# queso_dip_v4_5.net
KiCad netlist of a schematic drawn in EAGLE
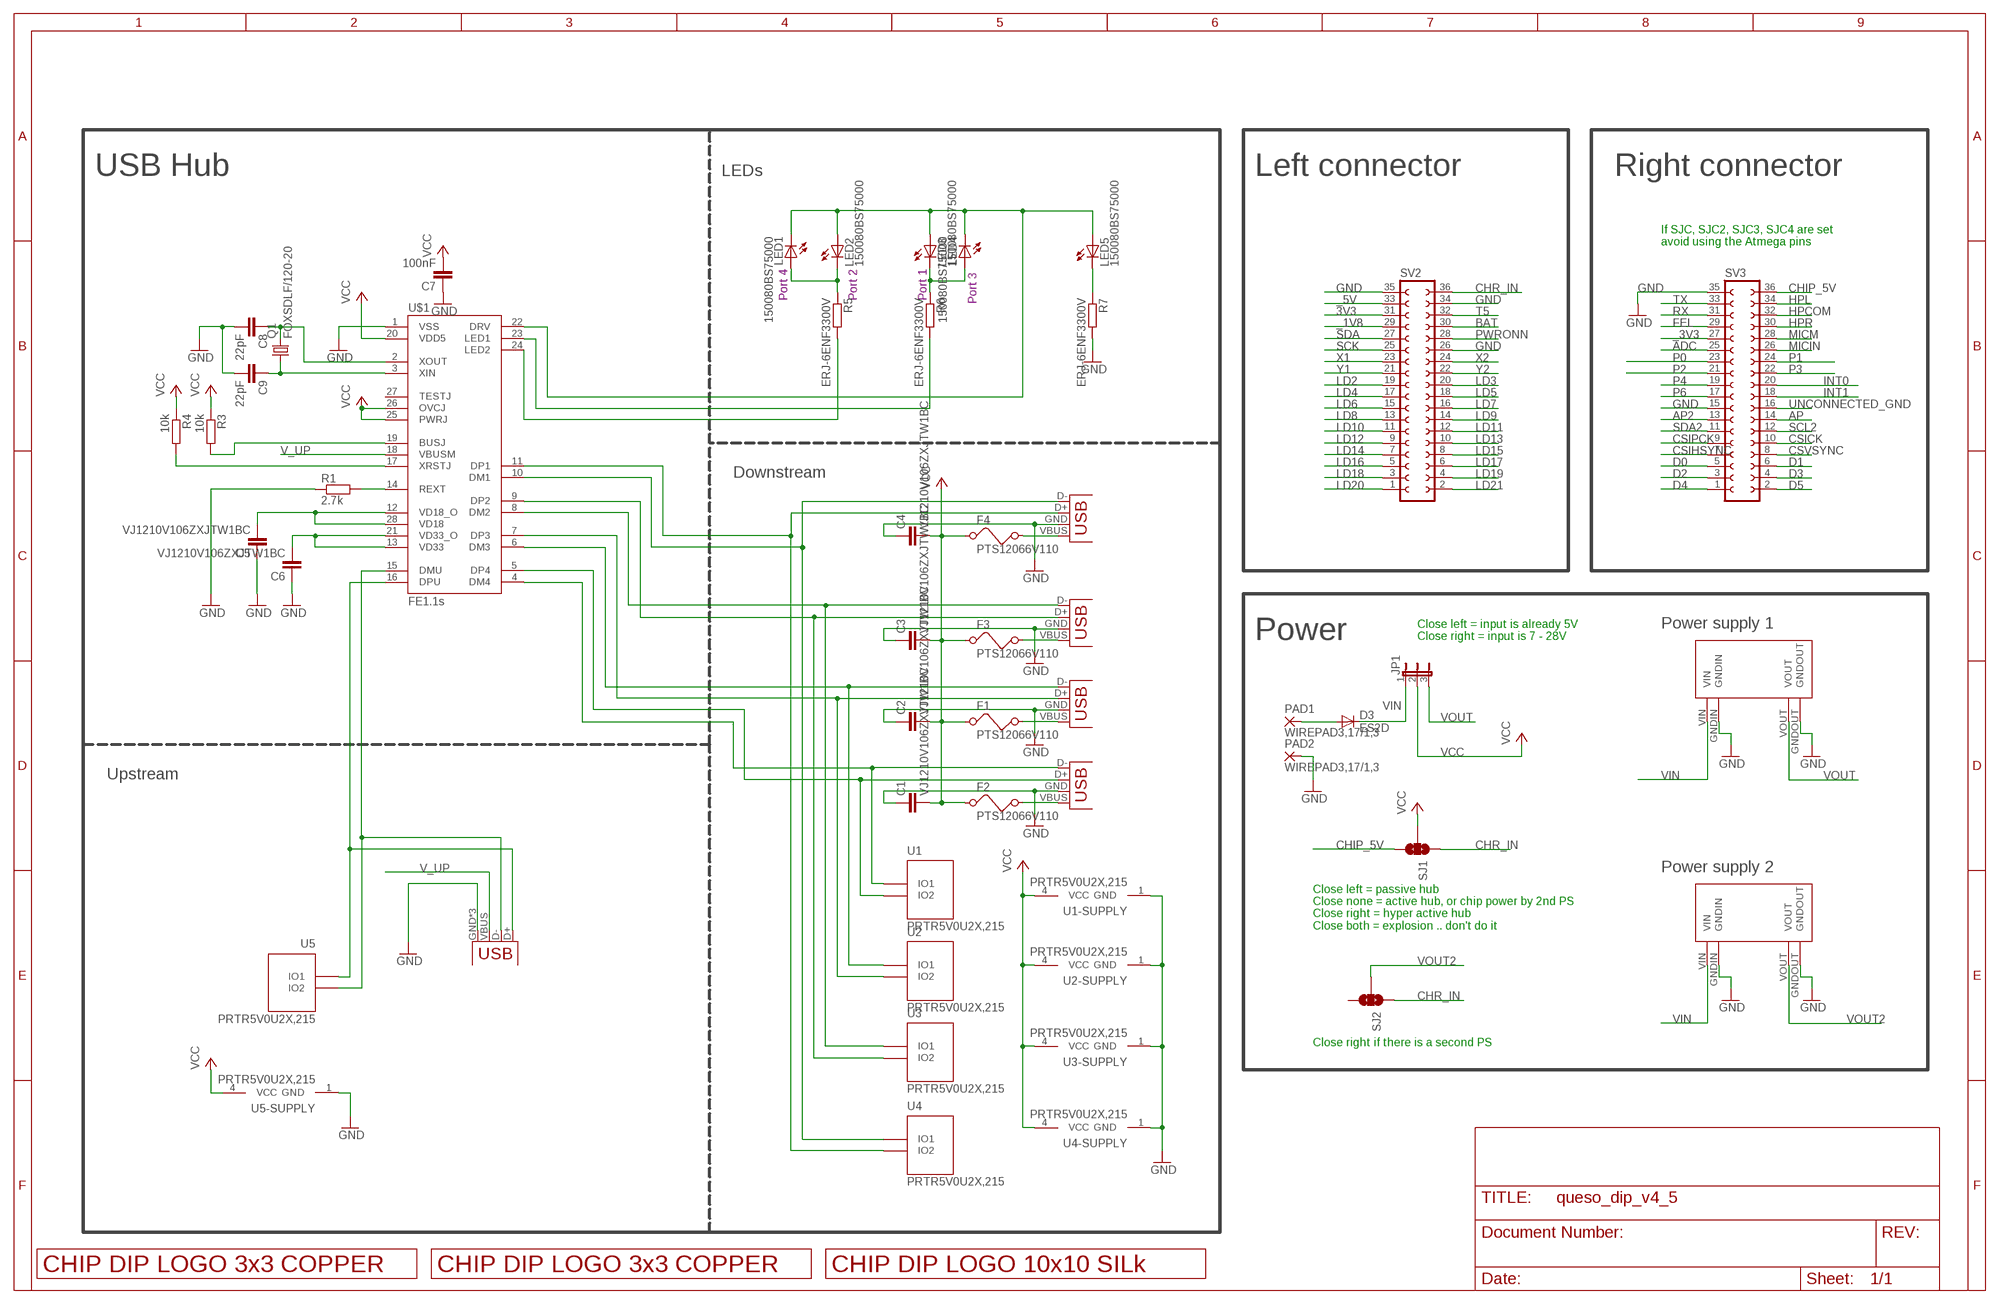
[diagram p0: schematic, sheet 1]

(export (version "E")
  (design (tool "Eeschema 10.0.6"))
  (components
    (comp (ref "C1")
      (value "VJ1210V106ZXJTW1BC")
      (footprint "eagle-import:C1210")
      (libsource (lib "eagle-import") (part "C-EUC1210"))
    )
    (comp (ref "C2")
      (value "VJ1210V106ZXJTW1BC")
      (footprint "eagle-import:C1210")
      (libsource (lib "eagle-import") (part "C-EUC1210"))
    )
    (comp (ref "C3")
      (value "VJ1210V106ZXJTW1BC")
      (footprint "eagle-import:C1210")
      (libsource (lib "eagle-import") (part "C-EUC1210"))
    )
    (comp (ref "C4")
      (value "VJ1210V106ZXJTW1BC")
      (footprint "eagle-import:C1210")
      (libsource (lib "eagle-import") (part "C-EUC1210"))
    )
    (comp (ref "C5")
      (value "VJ1210V106ZXJTW1BC")
      (footprint "eagle-import:C1210")
      (libsource (lib "eagle-import") (part "C-EUC1210"))
    )
    (comp (ref "C6")
      (value "VJ1210V106ZXJTW1BC")
      (footprint "eagle-import:C1210")
      (libsource (lib "eagle-import") (part "C-EUC1210"))
    )
    (comp (ref "C7")
      (value "100nF")
      (footprint "eagle-import:C0805")
      (libsource (lib "eagle-import") (part "C-EUC0805"))
    )
    (comp (ref "C8")
      (value "22pF")
      (footprint "eagle-import:C0805")
      (libsource (lib "eagle-import") (part "C-EUC0805"))
    )
    (comp (ref "C9")
      (value "22pF")
      (footprint "eagle-import:C0805")
      (libsource (lib "eagle-import") (part "C-EUC0805"))
    )
    (comp (ref "D3")
      (value "ES2D")
      (footprint "eagle-import:SMB")
      (libsource (lib "eagle-import") (part "ES2D"))
    )
    (comp (ref "F1")
      (value "PTS12066V110")
      (footprint "eagle-import:1210")
      (libsource (lib "eagle-import") (part "FUSED"))
    )
    (comp (ref "F2")
      (value "PTS12066V110")
      (footprint "eagle-import:1210")
      (libsource (lib "eagle-import") (part "FUSED"))
    )
    (comp (ref "F3")
      (value "PTS12066V110")
      (footprint "eagle-import:1210")
      (libsource (lib "eagle-import") (part "FUSED"))
    )
    (comp (ref "F4")
      (value "PTS12066V110")
      (footprint "eagle-import:1210")
      (libsource (lib "eagle-import") (part "FUSED"))
    )
    (comp (ref "JP1")
      (value "JP2E")
      (footprint "eagle-import:JP2")
      (libsource (lib "eagle-import") (part "JP2E"))
    )
    (comp (ref "LED1")
      (value "150080BS75000")
      (footprint "eagle-import:CHIP-LED0805")
      (libsource (lib "eagle-import") (part "LEDCHIP-LED0805"))
    )
    (comp (ref "LED2")
      (value "150080BS75000")
      (footprint "eagle-import:CHIP-LED0805")
      (libsource (lib "eagle-import") (part "LEDCHIP-LED0805"))
    )
    (comp (ref "LED3")
      (value "150080BS75000")
      (footprint "eagle-import:CHIP-LED0805")
      (libsource (lib "eagle-import") (part "LEDCHIP-LED0805"))
    )
    (comp (ref "LED4")
      (value "150080BS75000")
      (footprint "eagle-import:CHIP-LED0805")
      (libsource (lib "eagle-import") (part "LEDCHIP-LED0805"))
    )
    (comp (ref "LED5")
      (value "150080BS75000")
      (footprint "eagle-import:CHIP-LED0805")
      (libsource (lib "eagle-import") (part "LEDCHIP-LED0805"))
    )
    (comp (ref "PAD1")
      (value "WIREPAD3,17/1,3")
      (footprint "eagle-import:3,17_1,3")
      (libsource (lib "eagle-import") (part "WIREPAD3,17/1,3"))
    )
    (comp (ref "PAD2")
      (value "WIREPAD3,17/1,3")
      (footprint "eagle-import:3,17_1,3")
      (libsource (lib "eagle-import") (part "WIREPAD3,17/1,3"))
    )
    (comp (ref "Q1")
      (value "FOXSDLF/120-20")
      (footprint "eagle-import:SM49")
      (libsource (lib "eagle-import") (part "CRYSTALSM49"))
    )
    (comp (ref "R1")
      (value "2.7k")
      (footprint "eagle-import:R0805")
      (libsource (lib "eagle-import") (part "R-EU_R0805"))
    )
    (comp (ref "R3")
      (value "10k")
      (footprint "eagle-import:R0805")
      (libsource (lib "eagle-import") (part "R-EU_R0805"))
    )
    (comp (ref "R4")
      (value "10k")
      (footprint "eagle-import:R0805")
      (libsource (lib "eagle-import") (part "R-EU_R0805"))
    )
    (comp (ref "R5")
      (value "ERJ-6ENF3300V")
      (footprint "eagle-import:R0805")
      (libsource (lib "eagle-import") (part "R-EU_R0805"))
    )
    (comp (ref "R6")
      (value "ERJ-6ENF3300V")
      (footprint "eagle-import:R0805")
      (libsource (lib "eagle-import") (part "R-EU_R0805"))
    )
    (comp (ref "R7")
      (value "ERJ-6ENF3300V")
      (footprint "eagle-import:R0805")
      (libsource (lib "eagle-import") (part "R-EU_R0805"))
    )
    (comp (ref "SJ1")
      (value "SOLDERJUMPER_2WAYT")
      (footprint "eagle-import:SJ_2")
      (libsource (lib "eagle-import") (part "SOLDERJUMPER_2WAYT"))
    )
    (comp (ref "SJ2")
      (value "SOLDERJUMPER_2WAYT")
      (footprint "eagle-import:SJ_2")
      (libsource (lib "eagle-import") (part "SOLDERJUMPER_2WAYT"))
    )
    (comp (ref "SV2")
      (value "FE18-2")
      (footprint "eagle-import:FE18-2")
      (libsource (lib "eagle-import") (part "FE18-2"))
    )
    (comp (ref "SV3")
      (value "FE18-2")
      (footprint "eagle-import:FE18-2")
      (libsource (lib "eagle-import") (part "FE18-2"))
    )
    (comp (ref "U$1")
      (value "FE1.1S")
      (footprint "eagle-import:FE1.1S_SSOP-28")
      (libsource (lib "eagle-import") (part "FE1.1S"))
    )
    (comp (ref "U$2")
      (value "LOGO_3X3_COPPER")
      (footprint "eagle-import:LOGO_3X3_COPPER")
      (libsource (lib "eagle-import") (part "LOGO_3X3_COPPER"))
    )
    (comp (ref "U$3")
      (value "MP1584EN")
      (footprint "eagle-import:MP1584EN")
      (libsource (lib "eagle-import") (part "MP1584EN"))
    )
    (comp (ref "U$4")
      (value "LOGO_3X3_COPPER")
      (footprint "eagle-import:LOGO_3X3_COPPER")
      (libsource (lib "eagle-import") (part "LOGO_3X3_COPPER"))
    )
    (comp (ref "U$5")
      (value "LOGO_10X10_SILK")
      (footprint "eagle-import:LOGO_10X10_SILK")
      (libsource (lib "eagle-import") (part "LOGO_10X10_SILK"))
    )
    (comp (ref "U$9")
      (value "MP1584EN")
      (footprint "eagle-import:MP1584EN")
      (libsource (lib "eagle-import") (part "MP1584EN"))
    )
    (comp (ref "U1")
      (value "PRTR5V0U2X,215")
      (footprint "eagle-import:SOT-143B")
      (fields (field (name "MANUFACTURER") "NXP Semiconductors"))
      (libsource (lib "eagle-import") (part "PRTR5V0U2X?"))
    )
    (comp (ref "U2")
      (value "PRTR5V0U2X,215")
      (footprint "eagle-import:SOT-143B")
      (fields (field (name "MANUFACTURER") "NXP Semiconductors"))
      (libsource (lib "eagle-import") (part "PRTR5V0U2X?"))
    )
    (comp (ref "U3")
      (value "PRTR5V0U2X,215")
      (footprint "eagle-import:SOT-143B")
      (fields (field (name "MANUFACTURER") "NXP Semiconductors"))
      (libsource (lib "eagle-import") (part "PRTR5V0U2X?"))
    )
    (comp (ref "U4")
      (value "PRTR5V0U2X,215")
      (footprint "eagle-import:SOT-143B")
      (fields (field (name "MANUFACTURER") "NXP Semiconductors"))
      (libsource (lib "eagle-import") (part "PRTR5V0U2X?"))
    )
    (comp (ref "U5")
      (value "PRTR5V0U2X,215")
      (footprint "eagle-import:SOT-143B")
      (fields (field (name "MANUFACTURER") "NXP Semiconductors"))
      (libsource (lib "eagle-import") (part "PRTR5V0U2X?"))
    )
    (comp (ref "USB")
      (value "USBUSB-MICROB-SMT-DIP")
      (footprint "eagle-import:USB-MICROB-SMT-DIP")
      (libsource (lib "eagle-import") (part "USBUSB-MICROB-SMT-DIP"))
    )
    (comp (ref "X1")
      (value "USB-A-HU")
      (footprint "eagle-import:USB-A-HU")
      (libsource (lib "eagle-import") (part "USB-A-HU"))
    )
    (comp (ref "X2")
      (value "USB-A-HU")
      (footprint "eagle-import:USB-A-HU")
      (libsource (lib "eagle-import") (part "USB-A-HU"))
    )
    (comp (ref "X3")
      (value "USB-A-HU")
      (footprint "eagle-import:USB-A-HU")
      (libsource (lib "eagle-import") (part "USB-A-HU"))
    )
    (comp (ref "X4")
      (value "USB-A-HU")
      (footprint "eagle-import:USB-A-HU")
      (libsource (lib "eagle-import") (part "USB-A-HU"))
    )
  )
  (nets
    (net (code "1") (name "/3V3") (class "Default")
      (node (ref "SV2") (pin "31") (pinfunction "31_31") (pintype "passive"))
    )
    (net (code "2") (name "/ADC") (class "Default")
      (node (ref "SV3") (pin "25") (pinfunction "25_25") (pintype "passive"))
    )
    (net (code "3") (name "/AP") (class "Default")
      (node (ref "SV3") (pin "14") (pinfunction "14_14") (pintype "passive"))
    )
    (net (code "4") (name "/AP2") (class "Default")
      (node (ref "SV3") (pin "13") (pinfunction "13_13") (pintype "passive"))
    )
    (net (code "5") (name "/BAT") (class "Default")
      (node (ref "SV2") (pin "30") (pinfunction "30_30") (pintype "passive"))
    )
    (net (code "6") (name "/CHIP_5V") (class "Default")
      (node (ref "SJ1") (pin "3") (pinfunction "3_3") (pintype "passive"))
      (node (ref "SV3") (pin "36") (pinfunction "36_36") (pintype "passive"))
    )
    (net (code "7") (name "/CHR_IN") (class "Default")
      (node (ref "SJ1") (pin "1") (pinfunction "1_1") (pintype "passive"))
      (node (ref "SJ2") (pin "1") (pinfunction "1_1") (pintype "passive"))
      (node (ref "SV2") (pin "36") (pinfunction "36_36") (pintype "passive"))
    )
    (net (code "8") (name "/CSICK") (class "Default")
      (node (ref "SV3") (pin "10") (pinfunction "10_10") (pintype "passive"))
    )
    (net (code "9") (name "/CSIHSYNC") (class "Default")
      (node (ref "SV3") (pin "7") (pinfunction "7_7") (pintype "passive"))
    )
    (net (code "10") (name "/CSIPCK") (class "Default")
      (node (ref "SV3") (pin "9") (pinfunction "9_9") (pintype "passive"))
    )
    (net (code "11") (name "/CSVSYNC") (class "Default")
      (node (ref "SV3") (pin "8") (pinfunction "8_8") (pintype "passive"))
    )
    (net (code "12") (name "/D0") (class "Default")
      (node (ref "SV3") (pin "5") (pinfunction "5_5") (pintype "passive"))
    )
    (net (code "13") (name "/D1") (class "Default")
      (node (ref "SV3") (pin "6") (pinfunction "6_6") (pintype "passive"))
    )
    (net (code "14") (name "/D2") (class "Default")
      (node (ref "SV3") (pin "3") (pinfunction "3_3") (pintype "passive"))
    )
    (net (code "15") (name "/D3") (class "Default")
      (node (ref "SV3") (pin "4") (pinfunction "4_4") (pintype "passive"))
    )
    (net (code "16") (name "/D4") (class "Default")
      (node (ref "SV3") (pin "1") (pinfunction "1_1") (pintype "passive"))
    )
    (net (code "17") (name "/D5") (class "Default")
      (node (ref "SV3") (pin "2") (pinfunction "2_2") (pintype "passive"))
    )
    (net (code "18") (name "/FEL") (class "Default")
      (node (ref "SV3") (pin "29") (pinfunction "29_29") (pintype "passive"))
    )
    (net (code "19") (name "/HPCOM") (class "Default")
      (node (ref "SV3") (pin "32") (pinfunction "32_32") (pintype "passive"))
    )
    (net (code "20") (name "/HPL") (class "Default")
      (node (ref "SV3") (pin "34") (pinfunction "34_34") (pintype "passive"))
    )
    (net (code "21") (name "/HPR") (class "Default")
      (node (ref "SV3") (pin "30") (pinfunction "30_30") (pintype "passive"))
    )
    (net (code "22") (name "/INT0") (class "Default")
      (node (ref "SV3") (pin "20") (pinfunction "20_20") (pintype "passive"))
    )
    (net (code "23") (name "/INT1") (class "Default")
      (node (ref "SV3") (pin "18") (pinfunction "18_18") (pintype "passive"))
    )
    (net (code "24") (name "/LD2") (class "Default")
      (node (ref "SV2") (pin "19") (pinfunction "19_19") (pintype "passive"))
    )
    (net (code "25") (name "/LD3") (class "Default")
      (node (ref "SV2") (pin "20") (pinfunction "20_20") (pintype "passive"))
    )
    (net (code "26") (name "/LD4") (class "Default")
      (node (ref "SV2") (pin "17") (pinfunction "17_17") (pintype "passive"))
    )
    (net (code "27") (name "/LD5") (class "Default")
      (node (ref "SV2") (pin "18") (pinfunction "18_18") (pintype "passive"))
    )
    (net (code "28") (name "/LD6") (class "Default")
      (node (ref "SV2") (pin "15") (pinfunction "15_15") (pintype "passive"))
    )
    (net (code "29") (name "/LD7") (class "Default")
      (node (ref "SV2") (pin "16") (pinfunction "16_16") (pintype "passive"))
    )
    (net (code "30") (name "/LD8") (class "Default")
      (node (ref "SV2") (pin "13") (pinfunction "13_13") (pintype "passive"))
    )
    (net (code "31") (name "/LD9") (class "Default")
      (node (ref "SV2") (pin "14") (pinfunction "14_14") (pintype "passive"))
    )
    (net (code "32") (name "/LD10") (class "Default")
      (node (ref "SV2") (pin "11") (pinfunction "11_11") (pintype "passive"))
    )
    (net (code "33") (name "/LD11") (class "Default")
      (node (ref "SV2") (pin "12") (pinfunction "12_12") (pintype "passive"))
    )
    (net (code "34") (name "/LD12") (class "Default")
      (node (ref "SV2") (pin "9") (pinfunction "9_9") (pintype "passive"))
    )
    (net (code "35") (name "/LD13") (class "Default")
      (node (ref "SV2") (pin "10") (pinfunction "10_10") (pintype "passive"))
    )
    (net (code "36") (name "/LD14") (class "Default")
      (node (ref "SV2") (pin "7") (pinfunction "7_7") (pintype "passive"))
    )
    (net (code "37") (name "/LD15") (class "Default")
      (node (ref "SV2") (pin "8") (pinfunction "8_8") (pintype "passive"))
    )
    (net (code "38") (name "/LD16") (class "Default")
      (node (ref "SV2") (pin "5") (pinfunction "5_5") (pintype "passive"))
    )
    (net (code "39") (name "/LD17") (class "Default")
      (node (ref "SV2") (pin "6") (pinfunction "6_6") (pintype "passive"))
    )
    (net (code "40") (name "/LD18") (class "Default")
      (node (ref "SV2") (pin "3") (pinfunction "3_3") (pintype "passive"))
    )
    (net (code "41") (name "/LD19") (class "Default")
      (node (ref "SV2") (pin "4") (pinfunction "4_4") (pintype "passive"))
    )
    (net (code "42") (name "/LD20") (class "Default")
      (node (ref "SV2") (pin "1") (pinfunction "1_1") (pintype "passive"))
    )
    (net (code "43") (name "/LD21") (class "Default")
      (node (ref "SV2") (pin "2") (pinfunction "2_2") (pintype "passive"))
    )
    (net (code "44") (name "/MICIN") (class "Default")
      (node (ref "SV3") (pin "26") (pinfunction "26_26") (pintype "passive"))
    )
    (net (code "45") (name "/MICM") (class "Default")
      (node (ref "SV3") (pin "28") (pinfunction "28_28") (pintype "passive"))
    )
    (net (code "46") (name "/P0") (class "Default")
      (node (ref "SV3") (pin "23") (pinfunction "23_23") (pintype "passive"))
    )
    (net (code "47") (name "/P1") (class "Default")
      (node (ref "SV3") (pin "24") (pinfunction "24_24") (pintype "passive"))
    )
    (net (code "48") (name "/P2") (class "Default")
      (node (ref "SV3") (pin "21") (pinfunction "21_21") (pintype "passive"))
    )
    (net (code "49") (name "/P3") (class "Default")
      (node (ref "SV3") (pin "22") (pinfunction "22_22") (pintype "passive"))
    )
    (net (code "50") (name "/P4") (class "Default")
      (node (ref "SV3") (pin "19") (pinfunction "19_19") (pintype "passive"))
    )
    (net (code "51") (name "/P6") (class "Default")
      (node (ref "SV3") (pin "17") (pinfunction "17_17") (pintype "passive"))
    )
    (net (code "52") (name "/PWRONN") (class "Default")
      (node (ref "SV2") (pin "28") (pinfunction "28_28") (pintype "passive"))
    )
    (net (code "53") (name "/RX") (class "Default")
      (node (ref "SV3") (pin "31") (pinfunction "31_31") (pintype "passive"))
    )
    (net (code "54") (name "/SCK") (class "Default")
      (node (ref "SV2") (pin "25") (pinfunction "25_25") (pintype "passive"))
    )
    (net (code "55") (name "/SCL2") (class "Default")
      (node (ref "SV3") (pin "12") (pinfunction "12_12") (pintype "passive"))
    )
    (net (code "56") (name "/SDA") (class "Default")
      (node (ref "SV2") (pin "27") (pinfunction "27_27") (pintype "passive"))
    )
    (net (code "57") (name "/SDA2") (class "Default")
      (node (ref "SV3") (pin "11") (pinfunction "11_11") (pintype "passive"))
    )
    (net (code "58") (name "/T5") (class "Default")
      (node (ref "SV2") (pin "32") (pinfunction "32_32") (pintype "passive"))
    )
    (net (code "59") (name "/TX") (class "Default")
      (node (ref "SV3") (pin "33") (pinfunction "33_33") (pintype "passive"))
    )
    (net (code "60") (name "/UNCONNECTED_GND") (class "Default")
      (node (ref "SV3") (pin "16") (pinfunction "16_16") (pintype "passive"))
    )
    (net (code "61") (name "/VIN") (class "Default")
      (node (ref "D3") (pin "C") (pinfunction "C_C") (pintype "passive"))
      (node (ref "JP1") (pin "1") (pinfunction "1_1") (pintype "passive"))
      (node (ref "U$3") (pin "VIN") (pinfunction "VIN_VIN") (pintype "power_in"))
      (node (ref "U$9") (pin "VIN") (pinfunction "VIN_VIN") (pintype "power_in"))
    )
    (net (code "62") (name "/VOUT") (class "Default")
      (node (ref "JP1") (pin "3") (pinfunction "3_3") (pintype "passive"))
      (node (ref "U$9") (pin "VOUT") (pinfunction "VOUT_VOUT") (pintype "power_in"))
    )
    (net (code "63") (name "/VOUT2") (class "Default")
      (node (ref "SJ2") (pin "2") (pinfunction "2_2") (pintype "passive"))
      (node (ref "U$3") (pin "VOUT") (pinfunction "VOUT_VOUT") (pintype "power_in"))
    )
    (net (code "64") (name "/V_UP") (class "Default")
      (node (ref "U$1") (pin "18") (pinfunction "VBUSM_18") (pintype "bidirectional"))
      (node (ref "USB") (pin "VBUS") (pinfunction "VBUS_VBUS") (pintype "bidirectional"))
    )
    (net (code "65") (name "/X1") (class "Default")
      (node (ref "SV2") (pin "23") (pinfunction "23_23") (pintype "passive"))
    )
    (net (code "66") (name "/X2") (class "Default")
      (node (ref "SV2") (pin "24") (pinfunction "24_24") (pintype "passive"))
    )
    (net (code "67") (name "/Y1") (class "Default")
      (node (ref "SV2") (pin "21") (pinfunction "21_21") (pintype "passive"))
    )
    (net (code "68") (name "/Y2") (class "Default")
      (node (ref "SV2") (pin "22") (pinfunction "22_22") (pintype "passive"))
    )
    (net (code "69") (name "/_1V8") (class "Default")
      (node (ref "SV2") (pin "29") (pinfunction "29_29") (pintype "passive"))
    )
    (net (code "70") (name "/_3V3") (class "Default")
      (node (ref "SV3") (pin "27") (pinfunction "27_27") (pintype "passive"))
    )
    (net (code "71") (name "/_5V") (class "Default")
      (node (ref "SV2") (pin "33") (pinfunction "33_33") (pintype "passive"))
    )
    (net (code "72") (name "GND") (class "Default")
      (node (ref "C1") (pin "1") (pinfunction "1_1") (pintype "passive"))
      (node (ref "C2") (pin "1") (pinfunction "1_1") (pintype "passive"))
      (node (ref "C3") (pin "1") (pinfunction "1_1") (pintype "passive"))
      (node (ref "C4") (pin "1") (pinfunction "1_1") (pintype "passive"))
      (node (ref "C5") (pin "1") (pinfunction "1_1") (pintype "passive"))
      (node (ref "C6") (pin "1") (pinfunction "1_1") (pintype "passive"))
      (node (ref "C7") (pin "1") (pinfunction "1_1") (pintype "passive"))
      (node (ref "C8") (pin "2") (pinfunction "2_2") (pintype "passive"))
      (node (ref "C9") (pin "2") (pinfunction "2_2") (pintype "passive"))
      (node (ref "PAD2") (pin "1") (pinfunction "P_1") (pintype "passive"))
      (node (ref "R1") (pin "1") (pinfunction "1_1") (pintype "passive"))
      (node (ref "R7") (pin "2") (pinfunction "2_2") (pintype "passive"))
      (node (ref "SV2") (pin "26") (pinfunction "26_26") (pintype "passive"))
      (node (ref "SV2") (pin "34") (pinfunction "34_34") (pintype "passive"))
      (node (ref "SV2") (pin "35") (pinfunction "35_35") (pintype "passive"))
      (node (ref "SV3") (pin "15") (pinfunction "15_15") (pintype "passive"))
      (node (ref "SV3") (pin "35") (pinfunction "35_35") (pintype "passive"))
      (node (ref "U$1") (pin "1") (pinfunction "VSS_1") (pintype "bidirectional"))
      (node (ref "U$3") (pin "GNDIN") (pinfunction "GNDIN_GNDIN") (pintype "power_in"))
      (node (ref "U$3") (pin "GNDOUT") (pinfunction "GNDOUT_GNDOUT") (pintype "power_in"))
      (node (ref "U$9") (pin "GNDIN") (pinfunction "GNDIN_GNDIN") (pintype "power_in"))
      (node (ref "U$9") (pin "GNDOUT") (pinfunction "GNDOUT_GNDOUT") (pintype "power_in"))
      (node (ref "U1") (pin "1") (pinfunction "GND_1") (pintype "bidirectional"))
      (node (ref "U2") (pin "1") (pinfunction "GND_1") (pintype "bidirectional"))
      (node (ref "U3") (pin "1") (pinfunction "GND_1") (pintype "bidirectional"))
      (node (ref "U4") (pin "1") (pinfunction "GND_1") (pintype "bidirectional"))
      (node (ref "U5") (pin "1") (pinfunction "GND_1") (pintype "bidirectional"))
      (node (ref "USB") (pin "GND") (pinfunction "GND_GND") (pintype "bidirectional"))
      (node (ref "USB") (pin "MT1") (pinfunction "GND_MT1") (pintype "bidirectional"))
      (node (ref "USB") (pin "MT2") (pinfunction "GND_MT2") (pintype "bidirectional"))
      (node (ref "X1") (pin "GND") (pinfunction "VBUS_GND") (pintype "bidirectional"))
      (node (ref "X2") (pin "GND") (pinfunction "VBUS_GND") (pintype "bidirectional"))
      (node (ref "X3") (pin "GND") (pinfunction "VBUS_GND") (pintype "bidirectional"))
      (node (ref "X4") (pin "GND") (pinfunction "VBUS_GND") (pintype "bidirectional"))
    )
    (net (code "73") (name "Net-(LED1-PadA)") (class "Default")
      (node (ref "LED1") (pin "A") (pinfunction "A_A") (pintype "passive"))
      (node (ref "LED2") (pin "C") (pinfunction "C_C") (pintype "passive"))
      (node (ref "R5") (pin "1") (pinfunction "1_1") (pintype "passive"))
    )
    (net (code "74") (name "Net-(LED3-PadC)") (class "Default")
      (node (ref "LED3") (pin "C") (pinfunction "C_C") (pintype "passive"))
      (node (ref "LED4") (pin "A") (pinfunction "A_A") (pintype "passive"))
      (node (ref "R6") (pin "1") (pinfunction "1_1") (pintype "passive"))
    )
    (net (code "75") (name "Net-(LED5-PadC)") (class "Default")
      (node (ref "LED5") (pin "C") (pinfunction "C_C") (pintype "passive"))
      (node (ref "R7") (pin "1") (pinfunction "1_1") (pintype "passive"))
    )
    (net (code "76") (name "Net-(PAD1-P)") (class "Default")
      (node (ref "D3") (pin "A") (pinfunction "A_A") (pintype "passive"))
      (node (ref "PAD1") (pin "1") (pinfunction "P_1") (pintype "passive"))
    )
    (net (code "77") (name "Net-(U$1-BUSJ)") (class "Default")
      (node (ref "R3") (pin "2") (pinfunction "2_2") (pintype "passive"))
      (node (ref "U$1") (pin "19") (pinfunction "BUSJ_19") (pintype "bidirectional"))
    )
    (net (code "78") (name "Net-(U$1-DM1)") (class "Default")
      (node (ref "U$1") (pin "10") (pinfunction "DM1_10") (pintype "bidirectional"))
      (node (ref "U4") (pin "2") (pinfunction "IO1_2") (pintype "bidirectional"))
      (node (ref "X4") (pin "D-") (pinfunction "D+_D-") (pintype "bidirectional"))
    )
    (net (code "79") (name "Net-(U$1-DM2)") (class "Default")
      (node (ref "U$1") (pin "8") (pinfunction "DM2_8") (pintype "bidirectional"))
      (node (ref "U3") (pin "2") (pinfunction "IO1_2") (pintype "bidirectional"))
      (node (ref "X3") (pin "D-") (pinfunction "D+_D-") (pintype "bidirectional"))
    )
    (net (code "80") (name "Net-(U$1-DM3)") (class "Default")
      (node (ref "U$1") (pin "6") (pinfunction "DM3_6") (pintype "bidirectional"))
      (node (ref "U2") (pin "2") (pinfunction "IO1_2") (pintype "bidirectional"))
      (node (ref "X2") (pin "D-") (pinfunction "D+_D-") (pintype "bidirectional"))
    )
    (net (code "81") (name "Net-(U$1-DM4)") (class "Default")
      (node (ref "U$1") (pin "4") (pinfunction "DM4_4") (pintype "bidirectional"))
      (node (ref "U1") (pin "2") (pinfunction "IO1_2") (pintype "bidirectional"))
      (node (ref "X1") (pin "D-") (pinfunction "D+_D-") (pintype "bidirectional"))
    )
    (net (code "82") (name "Net-(U$1-DMU)") (class "Default")
      (node (ref "U$1") (pin "15") (pinfunction "DMU_15") (pintype "bidirectional"))
      (node (ref "U5") (pin "3") (pinfunction "IO2_3") (pintype "bidirectional"))
      (node (ref "USB") (pin "D-") (pinfunction "D-_D-") (pintype "bidirectional"))
    )
    (net (code "83") (name "Net-(U$1-DP1)") (class "Default")
      (node (ref "U$1") (pin "11") (pinfunction "DP1_11") (pintype "bidirectional"))
      (node (ref "U4") (pin "3") (pinfunction "IO2_3") (pintype "bidirectional"))
      (node (ref "X4") (pin "D+") (pinfunction "D-_D+") (pintype "bidirectional"))
    )
    (net (code "84") (name "Net-(U$1-DP2)") (class "Default")
      (node (ref "U$1") (pin "9") (pinfunction "DP2_9") (pintype "bidirectional"))
      (node (ref "U3") (pin "3") (pinfunction "IO2_3") (pintype "bidirectional"))
      (node (ref "X3") (pin "D+") (pinfunction "D-_D+") (pintype "bidirectional"))
    )
    (net (code "85") (name "Net-(U$1-DP3)") (class "Default")
      (node (ref "U$1") (pin "7") (pinfunction "DP3_7") (pintype "bidirectional"))
      (node (ref "U2") (pin "3") (pinfunction "IO2_3") (pintype "bidirectional"))
      (node (ref "X2") (pin "D+") (pinfunction "D-_D+") (pintype "bidirectional"))
    )
    (net (code "86") (name "Net-(U$1-DP4)") (class "Default")
      (node (ref "U$1") (pin "5") (pinfunction "DP4_5") (pintype "bidirectional"))
      (node (ref "U1") (pin "3") (pinfunction "IO2_3") (pintype "bidirectional"))
      (node (ref "X1") (pin "D+") (pinfunction "D-_D+") (pintype "bidirectional"))
    )
    (net (code "87") (name "Net-(U$1-DPU)") (class "Default")
      (node (ref "U$1") (pin "16") (pinfunction "DPU_16") (pintype "bidirectional"))
      (node (ref "U5") (pin "2") (pinfunction "IO1_2") (pintype "bidirectional"))
      (node (ref "USB") (pin "D+") (pinfunction "D+_D+") (pintype "bidirectional"))
    )
    (net (code "88") (name "Net-(U$1-DRV)") (class "Default")
      (node (ref "LED1") (pin "C") (pinfunction "C_C") (pintype "passive"))
      (node (ref "LED2") (pin "A") (pinfunction "A_A") (pintype "passive"))
      (node (ref "LED3") (pin "A") (pinfunction "A_A") (pintype "passive"))
      (node (ref "LED4") (pin "C") (pinfunction "C_C") (pintype "passive"))
      (node (ref "LED5") (pin "A") (pinfunction "A_A") (pintype "passive"))
      (node (ref "U$1") (pin "22") (pinfunction "DRV_22") (pintype "bidirectional"))
    )
    (net (code "89") (name "Net-(U$1-LED1)") (class "Default")
      (node (ref "R6") (pin "2") (pinfunction "2_2") (pintype "passive"))
      (node (ref "U$1") (pin "23") (pinfunction "LED1_23") (pintype "bidirectional"))
    )
    (net (code "90") (name "Net-(U$1-LED2)") (class "Default")
      (node (ref "R5") (pin "2") (pinfunction "2_2") (pintype "passive"))
      (node (ref "U$1") (pin "24") (pinfunction "LED2_24") (pintype "bidirectional"))
    )
    (net (code "91") (name "Net-(U$1-REXT)") (class "Default")
      (node (ref "R1") (pin "2") (pinfunction "2_2") (pintype "passive"))
      (node (ref "U$1") (pin "14") (pinfunction "REXT_14") (pintype "bidirectional"))
    )
    (net (code "92") (name "Net-(U$1-VD18)") (class "Default")
      (node (ref "C5") (pin "2") (pinfunction "2_2") (pintype "passive"))
      (node (ref "U$1") (pin "12") (pinfunction "VD18_O_12") (pintype "bidirectional"))
      (node (ref "U$1") (pin "28") (pinfunction "VD18_28") (pintype "bidirectional"))
    )
    (net (code "93") (name "Net-(U$1-VD33)") (class "Default")
      (node (ref "C6") (pin "2") (pinfunction "2_2") (pintype "passive"))
      (node (ref "U$1") (pin "13") (pinfunction "VD33_13") (pintype "bidirectional"))
      (node (ref "U$1") (pin "21") (pinfunction "VD33_O_21") (pintype "bidirectional"))
    )
    (net (code "94") (name "Net-(U$1-XIN)") (class "Default")
      (node (ref "C9") (pin "1") (pinfunction "1_1") (pintype "passive"))
      (node (ref "Q1") (pin "1") (pinfunction "1_1") (pintype "passive"))
      (node (ref "U$1") (pin "3") (pinfunction "XIN_3") (pintype "bidirectional"))
    )
    (net (code "95") (name "Net-(U$1-XOUT)") (class "Default")
      (node (ref "C8") (pin "1") (pinfunction "1_1") (pintype "passive"))
      (node (ref "Q1") (pin "2") (pinfunction "2_2") (pintype "passive"))
      (node (ref "U$1") (pin "2") (pinfunction "XOUT_2") (pintype "bidirectional"))
    )
    (net (code "96") (name "Net-(U$1-XRSTJ)") (class "Default")
      (node (ref "R4") (pin "2") (pinfunction "2_2") (pintype "passive"))
      (node (ref "U$1") (pin "17") (pinfunction "XRSTJ_17") (pintype "bidirectional"))
    )
    (net (code "97") (name "Net-(X1-GND)") (class "Default")
      (node (ref "F2") (pin "2") (pinfunction "2_2") (pintype "passive"))
      (node (ref "X1") (pin "VBUS") (pinfunction "GND_VBUS") (pintype "bidirectional"))
    )
    (net (code "98") (name "Net-(X2-GND)") (class "Default")
      (node (ref "F1") (pin "2") (pinfunction "2_2") (pintype "passive"))
      (node (ref "X2") (pin "VBUS") (pinfunction "GND_VBUS") (pintype "bidirectional"))
    )
    (net (code "99") (name "Net-(X3-GND)") (class "Default")
      (node (ref "F3") (pin "2") (pinfunction "2_2") (pintype "passive"))
      (node (ref "X3") (pin "VBUS") (pinfunction "GND_VBUS") (pintype "bidirectional"))
    )
    (net (code "100") (name "Net-(X4-GND)") (class "Default")
      (node (ref "F4") (pin "2") (pinfunction "2_2") (pintype "passive"))
      (node (ref "X4") (pin "VBUS") (pinfunction "GND_VBUS") (pintype "bidirectional"))
    )
    (net (code "101") (name "VCC") (class "Default")
      (node (ref "C1") (pin "2") (pinfunction "2_2") (pintype "passive"))
      (node (ref "C2") (pin "2") (pinfunction "2_2") (pintype "passive"))
      (node (ref "C3") (pin "2") (pinfunction "2_2") (pintype "passive"))
      (node (ref "C4") (pin "2") (pinfunction "2_2") (pintype "passive"))
      (node (ref "C7") (pin "2") (pinfunction "2_2") (pintype "passive"))
      (node (ref "F1") (pin "1") (pinfunction "1_1") (pintype "passive"))
      (node (ref "F2") (pin "1") (pinfunction "1_1") (pintype "passive"))
      (node (ref "F3") (pin "1") (pinfunction "1_1") (pintype "passive"))
      (node (ref "F4") (pin "1") (pinfunction "1_1") (pintype "passive"))
      (node (ref "JP1") (pin "2") (pinfunction "2_2") (pintype "passive"))
      (node (ref "R3") (pin "1") (pinfunction "1_1") (pintype "passive"))
      (node (ref "R4") (pin "1") (pinfunction "1_1") (pintype "passive"))
      (node (ref "SJ1") (pin "2") (pinfunction "2_2") (pintype "passive"))
      (node (ref "U$1") (pin "20") (pinfunction "VDD5_20") (pintype "bidirectional"))
      (node (ref "U$1") (pin "25") (pinfunction "PWRJ_25") (pintype "bidirectional"))
      (node (ref "U$1") (pin "26") (pinfunction "OVCJ_26") (pintype "bidirectional"))
      (node (ref "U1") (pin "4") (pinfunction "VCC_4") (pintype "bidirectional"))
      (node (ref "U2") (pin "4") (pinfunction "VCC_4") (pintype "bidirectional"))
      (node (ref "U3") (pin "4") (pinfunction "VCC_4") (pintype "bidirectional"))
      (node (ref "U4") (pin "4") (pinfunction "VCC_4") (pintype "bidirectional"))
      (node (ref "U5") (pin "4") (pinfunction "VCC_4") (pintype "bidirectional"))
    )
    (net (code "102") (name "unconnected-(SJ2-Pad3)") (class "Default")
      (node (ref "SJ2") (pin "3") (pinfunction "3_3") (pintype "passive"))
    )
    (net (code "103") (name "unconnected-(U$1-TESTJ-Pad27)") (class "Default")
      (node (ref "U$1") (pin "27") (pinfunction "TESTJ_27") (pintype "bidirectional"))
    )
  )
)
